# thrust-measuring-stand-schematic-r1_0.net
KiCad netlist of a schematic drawn in EasyEDA
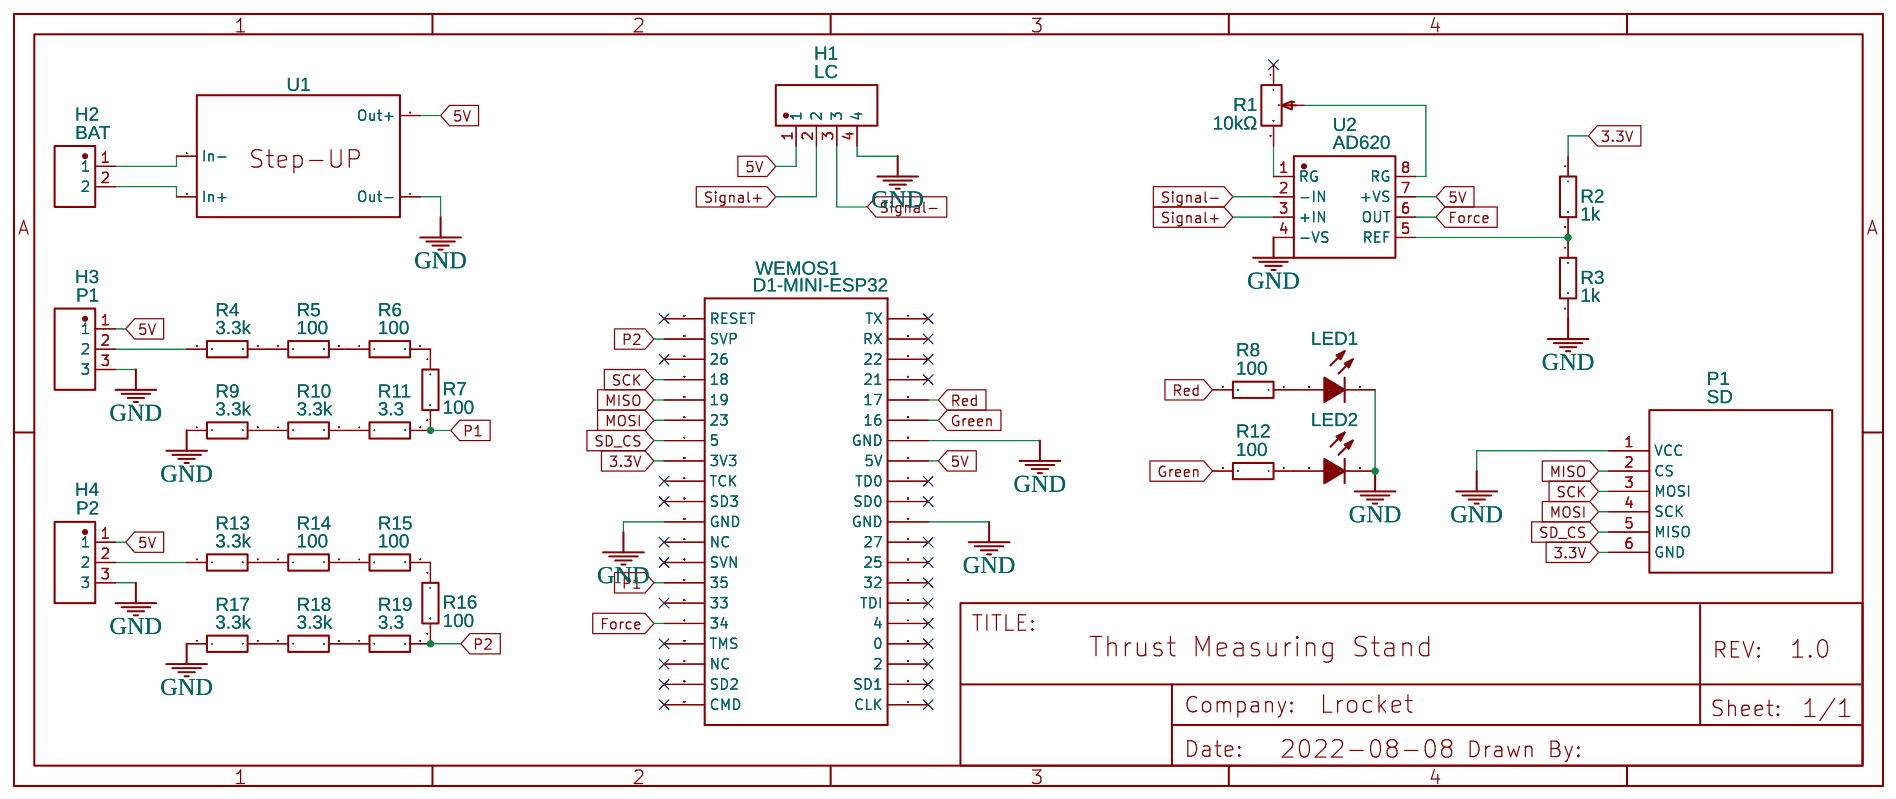
[diagram p0: schematic sheet]

(export (version "E")
  (design (tool "Eeschema 10.0.6"))
  (components
    (comp (ref "H1")
      (value "LC")
      (fields
        (field (name "BOM_Manufacturer Part") "KH-2.54PH180-1X4P-L11.5")
        (field (name "BOM_Supplier Part") "C2905435")
      )
      (libsource (lib "") (part "KH-2.54PH180-1X4P-L11.5"))
    )
    (comp (ref "H2")
      (value "BAT")
      (fields
        (field (name "BOM_Manufacturer Part") "1125-2102G0S110C005")
        (field (name "BOM_Supplier Part") "C721451")
      )
      (libsource (lib "") (part "1125-2102G0S110C005"))
    )
    (comp (ref "H3")
      (value "P1")
      (fields (field (name "BOM_Manufacturer Part") "FH-00306") (field (name "BOM_Supplier Part") "C2685109"))
      (libsource (lib "") (part "FH-00306"))
    )
    (comp (ref "H4")
      (value "P2")
      (fields (field (name "BOM_Manufacturer Part") "FH-00306") (field (name "BOM_Supplier Part") "C2685109"))
      (libsource (lib "") (part "FH-00306"))
    )
    (comp (ref "LED1")
      (value "Red")
      (fields
        (field (name "BOM_Manufacturer Part") "333-2SURD/S530-A3")
        (field (name "BOM_Supplier Part") "C87271")
      )
      (libsource (lib "") (part "333-2SURD/S530-A3"))
    )
    (comp (ref "LED2")
      (value "Green")
      (fields
        (field (name "BOM_Manufacturer Part") "333-2SURD/S530-A3")
        (field (name "BOM_Supplier Part") "C87271")
      )
      (libsource (lib "") (part "333-2SURD/S530-A3"))
    )
    (comp (ref "P1") (value "SD") (libsource (lib "") (part "Micro SD Card Module 3.3V V")))
    (comp (ref "R1")
      (value "10kΩ")
      (fields
        (field (name "BOM_Manufacturer Part") "3296W-1-204")
        (field (name "BOM_Supplier Part") "C330436")
      )
      (libsource (lib "") (part "3296W-1-204_C330436"))
    )
    (comp (ref "R2")
      (value "1k")
      (fields
        (field (name "BOM_Manufacturer Part") "AECR0603F390KK9")
        (field (name "BOM_Supplier Part") "C352324")
      )
      (libsource (lib "") (part "AECR0603F390KK9_1"))
    )
    (comp (ref "R3")
      (value "1k")
      (fields
        (field (name "BOM_Manufacturer Part") "AECR0603F390KK9")
        (field (name "BOM_Supplier Part") "C352324")
      )
      (libsource (lib "") (part "AECR0603F390KK9_1"))
    )
    (comp (ref "R4")
      (value "3.3k")
      (fields
        (field (name "BOM_Manufacturer Part") "AECR0603F390KK9")
        (field (name "BOM_Supplier Part") "C352324")
      )
      (libsource (lib "") (part "AECR0603F390KK9"))
    )
    (comp (ref "R5")
      (value "100")
      (fields
        (field (name "BOM_Manufacturer Part") "AECR0603F390KK9")
        (field (name "BOM_Supplier Part") "C352324")
      )
      (libsource (lib "") (part "AECR0603F390KK9"))
    )
    (comp (ref "R6")
      (value "100")
      (fields
        (field (name "BOM_Manufacturer Part") "AECR0603F390KK9")
        (field (name "BOM_Supplier Part") "C352324")
      )
      (libsource (lib "") (part "AECR0603F390KK9"))
    )
    (comp (ref "R7")
      (value "100")
      (fields
        (field (name "BOM_Manufacturer Part") "AECR0603F390KK9")
        (field (name "BOM_Supplier Part") "C352324")
      )
      (libsource (lib "") (part "AECR0603F390KK9_1"))
    )
    (comp (ref "R8")
      (value "100")
      (fields
        (field (name "BOM_Manufacturer Part") "AECR0603F390KK9")
        (field (name "BOM_Supplier Part") "C352324")
      )
      (libsource (lib "") (part "AECR0603F390KK9_2"))
    )
    (comp (ref "R9")
      (value "3.3k")
      (fields
        (field (name "BOM_Manufacturer Part") "AECR0603F390KK9")
        (field (name "BOM_Supplier Part") "C352324")
      )
      (libsource (lib "") (part "AECR0603F390KK9"))
    )
    (comp (ref "R10")
      (value "3.3k")
      (fields
        (field (name "BOM_Manufacturer Part") "AECR0603F390KK9")
        (field (name "BOM_Supplier Part") "C352324")
      )
      (libsource (lib "") (part "AECR0603F390KK9"))
    )
    (comp (ref "R11")
      (value "3.3")
      (fields
        (field (name "BOM_Manufacturer Part") "AECR0603F390KK9")
        (field (name "BOM_Supplier Part") "C352324")
      )
      (libsource (lib "") (part "AECR0603F390KK9"))
    )
    (comp (ref "R12")
      (value "100")
      (fields
        (field (name "BOM_Manufacturer Part") "AECR0603F390KK9")
        (field (name "BOM_Supplier Part") "C352324")
      )
      (libsource (lib "") (part "AECR0603F390KK9_2"))
    )
    (comp (ref "R13")
      (value "3.3k")
      (fields
        (field (name "BOM_Manufacturer Part") "AECR0603F390KK9")
        (field (name "BOM_Supplier Part") "C352324")
      )
      (libsource (lib "") (part "AECR0603F390KK9"))
    )
    (comp (ref "R14")
      (value "100")
      (fields
        (field (name "BOM_Manufacturer Part") "AECR0603F390KK9")
        (field (name "BOM_Supplier Part") "C352324")
      )
      (libsource (lib "") (part "AECR0603F390KK9"))
    )
    (comp (ref "R15")
      (value "100")
      (fields
        (field (name "BOM_Manufacturer Part") "AECR0603F390KK9")
        (field (name "BOM_Supplier Part") "C352324")
      )
      (libsource (lib "") (part "AECR0603F390KK9"))
    )
    (comp (ref "R16")
      (value "100")
      (fields
        (field (name "BOM_Manufacturer Part") "AECR0603F390KK9")
        (field (name "BOM_Supplier Part") "C352324")
      )
      (libsource (lib "") (part "AECR0603F390KK9_1"))
    )
    (comp (ref "R17")
      (value "3.3k")
      (fields
        (field (name "BOM_Manufacturer Part") "AECR0603F390KK9")
        (field (name "BOM_Supplier Part") "C352324")
      )
      (libsource (lib "") (part "AECR0603F390KK9"))
    )
    (comp (ref "R18")
      (value "3.3k")
      (fields
        (field (name "BOM_Manufacturer Part") "AECR0603F390KK9")
        (field (name "BOM_Supplier Part") "C352324")
      )
      (libsource (lib "") (part "AECR0603F390KK9"))
    )
    (comp (ref "R19")
      (value "3.3")
      (fields
        (field (name "BOM_Manufacturer Part") "AECR0603F390KK9")
        (field (name "BOM_Supplier Part") "C352324")
      )
      (libsource (lib "") (part "AECR0603F390KK9"))
    )
    (comp (ref "U1")
      (value "Mini Step-Up")
      (fields (field (name "BOM_Supplier Part") "B08HQQ32M2"))
      (libsource (lib "") (part "Mini Step-Up"))
    )
    (comp (ref "U2")
      (value "AD620")
      (fields
        (field (name "BOM_Manufacturer Part") "AD620SQ/883B")
        (field (name "BOM_Supplier Part") "C514229")
      )
      (libsource (lib "") (part "AD620SQ/883B"))
    )
    (comp (ref "WEMOS1") (value "D1-MINI-ESP32") (libsource (lib "") (part "D1-MINI-Esp32")))
  )
  (nets
    (net (code "1") (name "3.3V") (class "Default")
      (node (ref "P1") (pin "6") (pinfunction "GND_6") (pintype "unspecified"))
      (node (ref "R2") (pin "1") (pinfunction "1_1") (pintype "unspecified"))
      (node (ref "WEMOS1") (pin "3V3") (pinfunction "3V3_3V3") (pintype "unspecified"))
    )
    (net (code "2") (name "5V") (class "Default")
      (node (ref "H1") (pin "1") (pinfunction "1_1") (pintype "unspecified"))
      (node (ref "H3") (pin "1") (pinfunction "1_1") (pintype "unspecified"))
      (node (ref "H4") (pin "1") (pinfunction "1_1") (pintype "unspecified"))
      (node (ref "U1") (pin "3") (pinfunction "Out+_3") (pintype "unspecified"))
      (node (ref "U2") (pin "7") (pinfunction "+VS_7") (pintype "unspecified"))
      (node (ref "WEMOS1") (pin "5V") (pinfunction "5V_5V") (pintype "unspecified"))
    )
    (net (code "3") (name "Force") (class "Default")
      (node (ref "U2") (pin "6") (pinfunction "OUT_6") (pintype "unspecified"))
      (node (ref "WEMOS1") (pin "34") (pinfunction "34_34") (pintype "unspecified"))
    )
    (net (code "4") (name "GND") (class "Default")
      (node (ref "H1") (pin "4") (pinfunction "4_4") (pintype "unspecified"))
      (node (ref "H3") (pin "3") (pinfunction "3_3") (pintype "unspecified"))
      (node (ref "H4") (pin "3") (pinfunction "3_3") (pintype "unspecified"))
      (node (ref "LED1") (pin "1") (pinfunction "C_1") (pintype "input"))
      (node (ref "LED2") (pin "1") (pinfunction "C_1") (pintype "input"))
      (node (ref "P1") (pin "1") (pinfunction "VCC_1") (pintype "unspecified"))
      (node (ref "R17") (pin "1") (pinfunction "1_1") (pintype "unspecified"))
      (node (ref "R3") (pin "2") (pinfunction "2_2") (pintype "unspecified"))
      (node (ref "R9") (pin "1") (pinfunction "1_1") (pintype "unspecified"))
      (node (ref "U1") (pin "4") (pinfunction "Out-_4") (pintype "unspecified"))
      (node (ref "U2") (pin "4") (pinfunction "-VS_4") (pintype "unspecified"))
      (node (ref "WEMOS1") (pin "GND") (pinfunction "GND_GND") (pintype "unspecified"))
    )
    (net (code "5") (name "Green") (class "Default")
      (node (ref "R12") (pin "2") (pinfunction "2_2") (pintype "unspecified"))
      (node (ref "WEMOS1") (pin "16") (pinfunction "16_16") (pintype "unspecified"))
    )
    (net (code "6") (name "MISO") (class "Default")
      (node (ref "P1") (pin "2") (pinfunction "CS_2") (pintype "unspecified"))
      (node (ref "WEMOS1") (pin "19") (pinfunction "19_19") (pintype "unspecified"))
    )
    (net (code "7") (name "MOSI") (class "Default")
      (node (ref "P1") (pin "4") (pinfunction "SCK_4") (pintype "unspecified"))
      (node (ref "WEMOS1") (pin "23") (pinfunction "23_23") (pintype "unspecified"))
    )
    (net (code "8") (name "Net-(H3-Pad2)") (class "Default")
      (node (ref "H3") (pin "2") (pinfunction "2_2") (pintype "unspecified"))
      (node (ref "R4") (pin "1") (pinfunction "1_1") (pintype "unspecified"))
    )
    (net (code "9") (name "Net-(H4-Pad2)") (class "Default")
      (node (ref "H4") (pin "2") (pinfunction "2_2") (pintype "unspecified"))
      (node (ref "R13") (pin "1") (pinfunction "1_1") (pintype "unspecified"))
    )
    (net (code "10") (name "Net-(LED1-A)") (class "Default")
      (node (ref "LED1") (pin "2") (pinfunction "A_2") (pintype "input"))
      (node (ref "R8") (pin "1") (pinfunction "1_1") (pintype "unspecified"))
    )
    (net (code "11") (name "Net-(LED2-A)") (class "Default")
      (node (ref "LED2") (pin "2") (pinfunction "A_2") (pintype "input"))
      (node (ref "R12") (pin "1") (pinfunction "1_1") (pintype "unspecified"))
    )
    (net (code "12") (name "Net-(R1-Pad2)") (class "Default")
      (node (ref "R1") (pin "2") (pinfunction "2_2") (pintype "input"))
      (node (ref "U2") (pin "8") (pinfunction "RG_8") (pintype "unspecified"))
    )
    (net (code "13") (name "Net-(R1-Pad3)") (class "Default")
      (node (ref "R1") (pin "3") (pinfunction "3_3") (pintype "input"))
      (node (ref "U2") (pin "1") (pinfunction "RG_1") (pintype "unspecified"))
    )
    (net (code "14") (name "Net-(R4-Pad2)") (class "Default")
      (node (ref "R4") (pin "2") (pinfunction "2_2") (pintype "unspecified"))
      (node (ref "R5") (pin "1") (pinfunction "1_1") (pintype "unspecified"))
    )
    (net (code "15") (name "Net-(R5-Pad2)") (class "Default")
      (node (ref "R5") (pin "2") (pinfunction "2_2") (pintype "unspecified"))
      (node (ref "R6") (pin "1") (pinfunction "1_1") (pintype "unspecified"))
    )
    (net (code "16") (name "Net-(R6-Pad2)") (class "Default")
      (node (ref "R6") (pin "2") (pinfunction "2_2") (pintype "unspecified"))
      (node (ref "R7") (pin "1") (pinfunction "1_1") (pintype "unspecified"))
    )
    (net (code "17") (name "Net-(R10-Pad1)") (class "Default")
      (node (ref "R10") (pin "1") (pinfunction "1_1") (pintype "unspecified"))
      (node (ref "R9") (pin "2") (pinfunction "2_2") (pintype "unspecified"))
    )
    (net (code "18") (name "Net-(R10-Pad2)") (class "Default")
      (node (ref "R10") (pin "2") (pinfunction "2_2") (pintype "unspecified"))
      (node (ref "R11") (pin "1") (pinfunction "1_1") (pintype "unspecified"))
    )
    (net (code "19") (name "Net-(R13-Pad2)") (class "Default")
      (node (ref "R13") (pin "2") (pinfunction "2_2") (pintype "unspecified"))
      (node (ref "R14") (pin "1") (pinfunction "1_1") (pintype "unspecified"))
    )
    (net (code "20") (name "Net-(R14-Pad2)") (class "Default")
      (node (ref "R14") (pin "2") (pinfunction "2_2") (pintype "unspecified"))
      (node (ref "R15") (pin "1") (pinfunction "1_1") (pintype "unspecified"))
    )
    (net (code "21") (name "Net-(R15-Pad2)") (class "Default")
      (node (ref "R15") (pin "2") (pinfunction "2_2") (pintype "unspecified"))
      (node (ref "R16") (pin "1") (pinfunction "1_1") (pintype "unspecified"))
    )
    (net (code "22") (name "Net-(R17-Pad2)") (class "Default")
      (node (ref "R17") (pin "2") (pinfunction "2_2") (pintype "unspecified"))
      (node (ref "R18") (pin "1") (pinfunction "1_1") (pintype "unspecified"))
    )
    (net (code "23") (name "Net-(R18-Pad2)") (class "Default")
      (node (ref "R18") (pin "2") (pinfunction "2_2") (pintype "unspecified"))
      (node (ref "R19") (pin "1") (pinfunction "1_1") (pintype "unspecified"))
    )
    (net (code "24") (name "Net-(U1-In+)") (class "Default")
      (node (ref "H2") (pin "2") (pinfunction "2_2") (pintype "unspecified"))
      (node (ref "U1") (pin "2") (pinfunction "In+_2") (pintype "unspecified"))
    )
    (net (code "25") (name "Net-(U1-In-)") (class "Default")
      (node (ref "H2") (pin "1") (pinfunction "1_1") (pintype "unspecified"))
      (node (ref "U1") (pin "1") (pinfunction "In-_1") (pintype "unspecified"))
    )
    (net (code "26") (name "Net-(U2-REF)") (class "Default")
      (node (ref "R2") (pin "2") (pinfunction "2_2") (pintype "unspecified"))
      (node (ref "R3") (pin "1") (pinfunction "1_1") (pintype "unspecified"))
      (node (ref "U2") (pin "5") (pinfunction "REF_5") (pintype "unspecified"))
    )
    (net (code "27") (name "P1") (class "Default")
      (node (ref "R11") (pin "2") (pinfunction "2_2") (pintype "unspecified"))
      (node (ref "R7") (pin "2") (pinfunction "2_2") (pintype "unspecified"))
      (node (ref "WEMOS1") (pin "35") (pinfunction "35_35") (pintype "unspecified"))
    )
    (net (code "28") (name "P2") (class "Default")
      (node (ref "R16") (pin "2") (pinfunction "2_2") (pintype "unspecified"))
      (node (ref "R19") (pin "2") (pinfunction "2_2") (pintype "unspecified"))
      (node (ref "WEMOS1") (pin "SVP") (pinfunction "SVP_SVP") (pintype "unspecified"))
    )
    (net (code "29") (name "Red") (class "Default")
      (node (ref "R8") (pin "2") (pinfunction "2_2") (pintype "unspecified"))
      (node (ref "WEMOS1") (pin "17") (pinfunction "17_17") (pintype "unspecified"))
    )
    (net (code "30") (name "SCK") (class "Default")
      (node (ref "P1") (pin "3") (pinfunction "MOSI_3") (pintype "unspecified"))
      (node (ref "WEMOS1") (pin "18") (pinfunction "18_18") (pintype "unspecified"))
    )
    (net (code "31") (name "SD_CS") (class "Default")
      (node (ref "P1") (pin "5") (pinfunction "MISO_5") (pintype "unspecified"))
      (node (ref "WEMOS1") (pin "5") (pinfunction "5_5") (pintype "unspecified"))
    )
    (net (code "32") (name "Signal+") (class "Default")
      (node (ref "H1") (pin "2") (pinfunction "2_2") (pintype "unspecified"))
      (node (ref "U2") (pin "3") (pinfunction "+IN_3") (pintype "unspecified"))
    )
    (net (code "33") (name "Signal-") (class "Default")
      (node (ref "H1") (pin "3") (pinfunction "3_3") (pintype "unspecified"))
      (node (ref "U2") (pin "2") (pinfunction "-IN_2") (pintype "unspecified"))
    )
    (net (code "34") (name "unconnected-(R1-Pad1)") (class "Default")
      (node (ref "R1") (pin "1") (pinfunction "1_1") (pintype "input+no_connect"))
    )
    (net (code "35") (name "unconnected-(WEMOS1-27-Pad25)") (class "Default")
      (node (ref "WEMOS1") (pin "25") (pinfunction "27_25") (pintype "unspecified+no_connect"))
    )
    (net (code "36") (name "unconnected-(WEMOS1-Pad0)") (class "Default")
      (node (ref "WEMOS1") (pin "0") (pinfunction "0_0") (pintype "unspecified+no_connect"))
    )
    (net (code "37") (name "unconnected-(WEMOS1-Pad2)") (class "Default")
      (node (ref "WEMOS1") (pin "2") (pinfunction "2_2") (pintype "unspecified+no_connect"))
    )
    (net (code "38") (name "unconnected-(WEMOS1-Pad4)") (class "Default")
      (node (ref "WEMOS1") (pin "4") (pinfunction "4_4") (pintype "unspecified+no_connect"))
    )
    (net (code "39") (name "unconnected-(WEMOS1-Pad21)") (class "Default")
      (node (ref "WEMOS1") (pin "21") (pinfunction "21_21") (pintype "unspecified+no_connect"))
    )
    (net (code "40") (name "unconnected-(WEMOS1-Pad22)") (class "Default")
      (node (ref "WEMOS1") (pin "22") (pinfunction "22_22") (pintype "unspecified+no_connect"))
    )
    (net (code "41") (name "unconnected-(WEMOS1-Pad25)") (class "Default")
      (node (ref "WEMOS1") (pin "25") (pinfunction "25_25") (pintype "unspecified+no_connect"))
    )
    (net (code "42") (name "unconnected-(WEMOS1-Pad26)") (class "Default")
      (node (ref "WEMOS1") (pin "26") (pinfunction "26_26") (pintype "unspecified+no_connect"))
    )
    (net (code "43") (name "unconnected-(WEMOS1-Pad32)") (class "Default")
      (node (ref "WEMOS1") (pin "32") (pinfunction "32_32") (pintype "unspecified+no_connect"))
    )
    (net (code "44") (name "unconnected-(WEMOS1-Pad33)") (class "Default")
      (node (ref "WEMOS1") (pin "33") (pinfunction "33_33") (pintype "unspecified+no_connect"))
    )
    (net (code "45") (name "unconnected-(WEMOS1-PadCLK)") (class "Default")
      (node (ref "WEMOS1") (pin "CLK") (pinfunction "CLK_CLK") (pintype "unspecified+no_connect"))
    )
    (net (code "46") (name "unconnected-(WEMOS1-PadCMD)") (class "Default")
      (node (ref "WEMOS1") (pin "CMD") (pinfunction "CMD_CMD") (pintype "unspecified+no_connect"))
    )
    (net (code "47") (name "unconnected-(WEMOS1-PadNC)") (class "Default")
      (node (ref "WEMOS1") (pin "NC") (pinfunction "NC_NC") (pintype "unspecified+no_connect"))
    )
    (net (code "48") (name "unconnected-(WEMOS1-PadNC)_1") (class "Default")
      (node (ref "WEMOS1") (pin "NC") (pinfunction "NC_NC") (pintype "unspecified+no_connect"))
    )
    (net (code "49") (name "unconnected-(WEMOS1-PadRESET)") (class "Default")
      (node (ref "WEMOS1") (pin "RESET") (pinfunction "RESET_RESET") (pintype "unspecified+no_connect"))
    )
    (net (code "50") (name "unconnected-(WEMOS1-PadRX)") (class "Default")
      (node (ref "WEMOS1") (pin "RX") (pinfunction "RX_RX") (pintype "unspecified+no_connect"))
    )
    (net (code "51") (name "unconnected-(WEMOS1-PadSD0)") (class "Default")
      (node (ref "WEMOS1") (pin "SD0") (pinfunction "SD0_SD0") (pintype "unspecified+no_connect"))
    )
    (net (code "52") (name "unconnected-(WEMOS1-PadSD1)") (class "Default")
      (node (ref "WEMOS1") (pin "SD1") (pinfunction "SD1_SD1") (pintype "unspecified+no_connect"))
    )
    (net (code "53") (name "unconnected-(WEMOS1-PadSD2)") (class "Default")
      (node (ref "WEMOS1") (pin "SD2") (pinfunction "SD2_SD2") (pintype "unspecified+no_connect"))
    )
    (net (code "54") (name "unconnected-(WEMOS1-PadSD3)") (class "Default")
      (node (ref "WEMOS1") (pin "SD3") (pinfunction "SD3_SD3") (pintype "unspecified+no_connect"))
    )
    (net (code "55") (name "unconnected-(WEMOS1-PadSVN)") (class "Default")
      (node (ref "WEMOS1") (pin "SVN") (pinfunction "SVN_SVN") (pintype "unspecified+no_connect"))
    )
    (net (code "56") (name "unconnected-(WEMOS1-PadTCK)") (class "Default")
      (node (ref "WEMOS1") (pin "TCK") (pinfunction "TCK_TCK") (pintype "unspecified+no_connect"))
    )
    (net (code "57") (name "unconnected-(WEMOS1-PadTD0)") (class "Default")
      (node (ref "WEMOS1") (pin "TD0") (pinfunction "TD0_TD0") (pintype "unspecified+no_connect"))
    )
    (net (code "58") (name "unconnected-(WEMOS1-PadTDI)") (class "Default")
      (node (ref "WEMOS1") (pin "TDI") (pinfunction "TDI_TDI") (pintype "unspecified+no_connect"))
    )
    (net (code "59") (name "unconnected-(WEMOS1-PadTMS)") (class "Default")
      (node (ref "WEMOS1") (pin "TMS") (pinfunction "TMS_TMS") (pintype "unspecified+no_connect"))
    )
    (net (code "60") (name "unconnected-(WEMOS1-PadTX)") (class "Default")
      (node (ref "WEMOS1") (pin "TX") (pinfunction "TX_TX") (pintype "unspecified+no_connect"))
    )
  )
)
